# AM-Crystal-RX.net
KiCad netlist of a schematic drawn in EAGLE
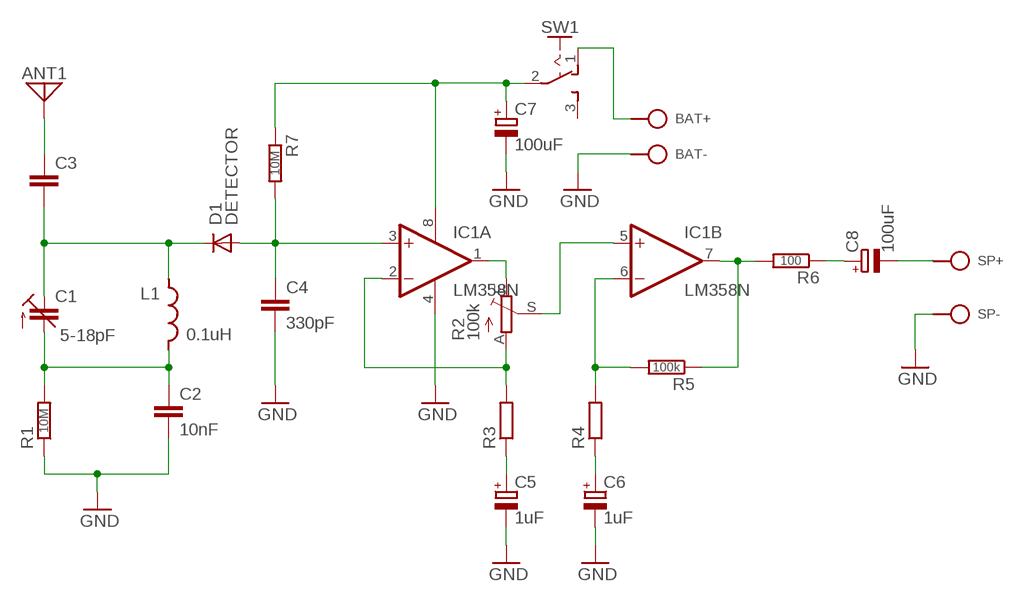
[diagram p0: schematic, sheet 1]

(export (version "E")
  (design (tool "Eeschema 10.0.6"))
  (components
    (comp (ref "ANT1")
      (value "ANT")
      (footprint "eagle-import:SPAD")
      (libsource (lib "eagle-import") (part "ANT"))
    )
    (comp (ref "BAT+")
      (value "BAT+")
      (footprint "eagle-import:SPAD")
      (libsource (lib "eagle-import") (part "SPAD"))
    )
    (comp (ref "BAT-")
      (value "BAT-")
      (footprint "eagle-import:SPAD")
      (libsource (lib "eagle-import") (part "SPAD"))
    )
    (comp (ref "C1")
      (value "5-18pF")
      (footprint "eagle-import:TRIM-2222-808")
      (libsource (lib "eagle-import") (part "C-TR-PH201272222-808-2PIN"))
    )
    (comp (ref "C2")
      (value "10nF")
      (footprint "eagle-import:C050-025X075")
      (libsource (lib "eagle-import") (part "C050-025X075"))
    )
    (comp (ref "C3")
      (value "C025-015X024")
      (footprint "eagle-import:C025-015X024")
      (libsource (lib "eagle-import") (part "C025-015X024"))
    )
    (comp (ref "C4")
      (value "330pF")
      (footprint "eagle-import:C050-024X044")
      (libsource (lib "eagle-import") (part "C050-024X044"))
    )
    (comp (ref "C5")
      (value "1uF")
      (footprint "eagle-import:E2,5-3")
      (libsource (lib "eagle-import") (part "CPOLE2,5-3"))
    )
    (comp (ref "C6")
      (value "1uF")
      (footprint "eagle-import:E2,5-3")
      (libsource (lib "eagle-import") (part "CPOLE2,5-3"))
    )
    (comp (ref "C7")
      (value "100uF")
      (footprint "eagle-import:E2,5-5")
      (libsource (lib "eagle-import") (part "CPOLE2.5-5"))
    )
    (comp (ref "C8")
      (value "100uF")
      (footprint "eagle-import:E2,5-5")
      (libsource (lib "eagle-import") (part "CPOLE2.5-5"))
    )
    (comp (ref "D1")
      (value "DETECTOR")
      (footprint "eagle-import:DO34-10")
      (libsource (lib "eagle-import") (part "1N414834-10"))
    )
    (comp (ref "IC1")
      (value "LM358N")
      (footprint "eagle-import:DIL08")
      (libsource (lib "eagle-import") (part "LM358N"))
    )
    (comp (ref "L1")
      (value "0.1uH")
      (footprint "eagle-import:L-04_10")
      (libsource (lib "eagle-import") (part "L-SHORT04/10"))
    )
    (comp (ref "R1")
      (value "10M")
      (footprint "eagle-import:0202_7-V")
      (libsource (lib "eagle-import") (part "R0202/7-V"))
    )
    (comp (ref "R2")
      (value "100k")
      (footprint "eagle-import:B64Y")
      (libsource (lib "eagle-import") (part "TRIM_EU-B64Y"))
    )
    (comp (ref "R3")
      (value "R0202/7")
      (footprint "eagle-import:0202_7")
      (libsource (lib "eagle-import") (part "R0202/7"))
    )
    (comp (ref "R4")
      (value "R0202/7")
      (footprint "eagle-import:0202_7")
      (libsource (lib "eagle-import") (part "R0202/7"))
    )
    (comp (ref "R5")
      (value "100k")
      (footprint "eagle-import:0202_7")
      (libsource (lib "eagle-import") (part "R0202/7"))
    )
    (comp (ref "R6")
      (value "100")
      (footprint "eagle-import:0202_7")
      (libsource (lib "eagle-import") (part "R0202/7"))
    )
    (comp (ref "R7")
      (value "10M")
      (footprint "eagle-import:0202_7")
      (libsource (lib "eagle-import") (part "R0202/7"))
    )
    (comp (ref "SP+")
      (value "SPKR+")
      (footprint "eagle-import:SPAD")
      (libsource (lib "eagle-import") (part "SPAD"))
    )
    (comp (ref "SP-")
      (value "SPKR-")
      (footprint "eagle-import:SPAD")
      (libsource (lib "eagle-import") (part "SPAD"))
    )
    (comp (ref "SW1")
      (value "SL-SW-1P-2T-H")
      (footprint "eagle-import:SLSW-1P2T-H")
      (libsource (lib "eagle-import") (part "SL-SW-1P-2T-H"))
    )
  )
  (nets
    (net (code "1") (name "GND") (class "Default")
      (node (ref "BAT-") (pin "1") (pinfunction "P$1_1") (pintype "bidirectional"))
      (node (ref "C2") (pin "2") (pinfunction "2_2") (pintype "passive"))
      (node (ref "C4") (pin "2") (pinfunction "2_2") (pintype "passive"))
      (node (ref "C5") (pin "-") (pinfunction "-_-") (pintype "passive"))
      (node (ref "C6") (pin "-") (pinfunction "-_-") (pintype "passive"))
      (node (ref "C7") (pin "-") (pinfunction "-_-") (pintype "passive"))
      (node (ref "IC1") (pin "4") (pinfunction "V-_4") (pintype "power_in"))
      (node (ref "R1") (pin "1") (pinfunction "1_1") (pintype "passive"))
      (node (ref "SP-") (pin "1") (pinfunction "P$1_1") (pintype "bidirectional"))
    )
    (net (code "2") (name "Net-(ANT1-Pad1)") (class "Default")
      (node (ref "ANT1") (pin "1") (pinfunction "1_1") (pintype "output"))
      (node (ref "C3") (pin "1") (pinfunction "1_1") (pintype "passive"))
    )
    (net (code "3") (name "Net-(BAT+-P$1)") (class "Default")
      (node (ref "BAT+") (pin "1") (pinfunction "P$1_1") (pintype "bidirectional"))
      (node (ref "SW1") (pin "1") (pinfunction "O_1") (pintype "passive"))
    )
    (net (code "4") (name "Net-(C1-A)") (class "Default")
      (node (ref "C1") (pin "1") (pinfunction "A_1") (pintype "passive"))
      (node (ref "C3") (pin "2") (pinfunction "2_2") (pintype "passive"))
      (node (ref "D1") (pin "C") (pinfunction "C_C") (pintype "passive"))
      (node (ref "L1") (pin "1") (pinfunction "1_1") (pintype "passive"))
    )
    (net (code "5") (name "Net-(C1-E)") (class "Default")
      (node (ref "C1") (pin "2") (pinfunction "E_2") (pintype "passive"))
      (node (ref "C2") (pin "1") (pinfunction "1_1") (pintype "passive"))
      (node (ref "L1") (pin "2") (pinfunction "2_2") (pintype "passive"))
      (node (ref "R1") (pin "2") (pinfunction "2_2") (pintype "passive"))
    )
    (net (code "6") (name "Net-(C5-Pad+)") (class "Default")
      (node (ref "C5") (pin "+") (pinfunction "+_+") (pintype "passive"))
      (node (ref "R3") (pin "1") (pinfunction "1_1") (pintype "passive"))
    )
    (net (code "7") (name "Net-(C6-Pad+)") (class "Default")
      (node (ref "C6") (pin "+") (pinfunction "+_+") (pintype "passive"))
      (node (ref "R4") (pin "1") (pinfunction "1_1") (pintype "passive"))
    )
    (net (code "8") (name "Net-(C8-Pad+)") (class "Default")
      (node (ref "C8") (pin "+") (pinfunction "+_+") (pintype "passive"))
      (node (ref "R6") (pin "1") (pinfunction "1_1") (pintype "passive"))
    )
    (net (code "9") (name "Net-(IC1A-+IN)") (class "Default")
      (node (ref "C4") (pin "1") (pinfunction "1_1") (pintype "passive"))
      (node (ref "D1") (pin "A") (pinfunction "A_A") (pintype "passive"))
      (node (ref "IC1") (pin "3") (pinfunction "+IN_3") (pintype "input"))
      (node (ref "R7") (pin "2") (pinfunction "2_2") (pintype "passive"))
    )
    (net (code "10") (name "Net-(IC1A--IN)") (class "Default")
      (node (ref "IC1") (pin "2") (pinfunction "-IN_2") (pintype "input"))
      (node (ref "R2") (pin "A") (pinfunction "A_A") (pintype "passive"))
      (node (ref "R3") (pin "2") (pinfunction "2_2") (pintype "passive"))
    )
    (net (code "11") (name "Net-(IC1A-OUT)") (class "Default")
      (node (ref "IC1") (pin "1") (pinfunction "OUT_1") (pintype "output"))
      (node (ref "R2") (pin "E") (pinfunction "E_E") (pintype "passive"))
    )
    (net (code "12") (name "Net-(IC1B-+IN)") (class "Default")
      (node (ref "IC1") (pin "5") (pinfunction "+IN_5") (pintype "input"))
      (node (ref "R2") (pin "S") (pinfunction "S_S") (pintype "passive"))
    )
    (net (code "13") (name "Net-(IC1B--IN)") (class "Default")
      (node (ref "IC1") (pin "6") (pinfunction "-IN_6") (pintype "input"))
      (node (ref "R4") (pin "2") (pinfunction "2_2") (pintype "passive"))
      (node (ref "R5") (pin "2") (pinfunction "2_2") (pintype "passive"))
    )
    (net (code "14") (name "Net-(IC1B-OUT)") (class "Default")
      (node (ref "IC1") (pin "7") (pinfunction "OUT_7") (pintype "output"))
      (node (ref "R5") (pin "1") (pinfunction "1_1") (pintype "passive"))
      (node (ref "R6") (pin "2") (pinfunction "2_2") (pintype "passive"))
    )
    (net (code "15") (name "Net-(IC1C-V+)") (class "Default")
      (node (ref "C7") (pin "+") (pinfunction "+_+") (pintype "passive"))
      (node (ref "IC1") (pin "8") (pinfunction "V+_8") (pintype "power_in"))
      (node (ref "R7") (pin "1") (pinfunction "1_1") (pintype "passive"))
      (node (ref "SW1") (pin "2") (pinfunction "P_2") (pintype "passive"))
    )
    (net (code "16") (name "Net-(SP+-P$1)") (class "Default")
      (node (ref "C8") (pin "-") (pinfunction "-_-") (pintype "passive"))
      (node (ref "SP+") (pin "1") (pinfunction "P$1_1") (pintype "bidirectional"))
    )
    (net (code "17") (name "unconnected-(SW1-S-Pad3)") (class "Default")
      (node (ref "SW1") (pin "3") (pinfunction "S_3") (pintype "passive"))
    )
  )
)
